# MicroSD.net
KiCad netlist of a schematic drawn in Altium Designer
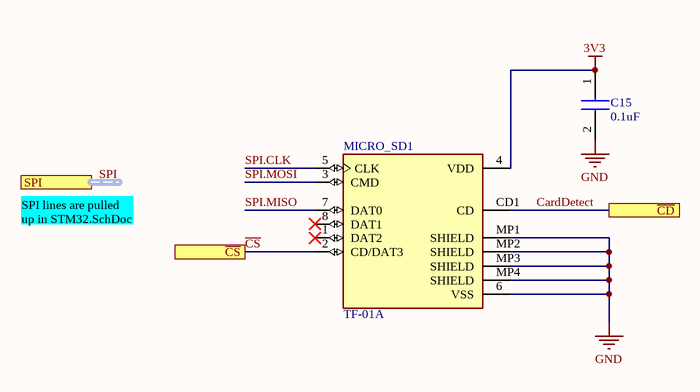
[diagram p0: MicroSD.SchDoc]

(export (version "E")
  (design (tool "Eeschema 10.0.6"))
  (components
    (comp (ref "C15")
      (value "0.1uF")
      (footprint "SamacSys:CAPC1005X55N")
      (description "0.1uF Ceramic Capacitor")
      (fields
        (field (name "MANUFACTURER_PART_NUMBER") "CL05B104KO5NNNC")
        (field (name "MOUSER PART NUMBER") "187-CL05B104KO5NNNC")
      )
      (libsource (lib "SamacSys") (part "CL05B104KO5NNNC"))
    )
    (comp (ref "MICRO_SD1")
      (value "TF-01A")
      (footprint "TF-01A")
      (description "Standard Card Edge Connectors")
      (fields (field (name "MF") "HRO Electronics Co., Ltd."))
      (libsource (lib "TF-01A") (part "TF-01A"))
    )
  )
  (nets
    (net (code "2") (name "/CardDetect") (class "Default")
      (node (ref "MICRO_SD1") (pin "CD1") (pinfunction "CD_CD1") (pintype "passive"))
    )
    (net (code "3") (name "/SPI.CLK") (class "Default")
      (node (ref "MICRO_SD1") (pin "5") (pinfunction "CLK_5") (pintype "bidirectional"))
    )
    (net (code "4") (name "/SPI.MISO") (class "Default")
      (node (ref "MICRO_SD1") (pin "7") (pinfunction "DAT0_7") (pintype "bidirectional"))
    )
    (net (code "5") (name "/SPI.MOSI") (class "Default")
      (node (ref "MICRO_SD1") (pin "3") (pinfunction "CMD_3") (pintype "bidirectional"))
    )
    (net (code "7") (name "/~{CS}") (class "Default")
      (node (ref "MICRO_SD1") (pin "2") (pinfunction "CD/DAT3_2") (pintype "bidirectional"))
    )
    (net (code "8") (name "3V3") (class "Default")
      (node (ref "C15") (pin "1") (pinfunction "1_1") (pintype "passive"))
      (node (ref "MICRO_SD1") (pin "4") (pinfunction "VDD_4") (pintype "power_in"))
    )
    (net (code "9") (name "GND") (class "Default")
      (node (ref "C15") (pin "2") (pinfunction "2_2") (pintype "passive"))
      (node (ref "MICRO_SD1") (pin "6") (pinfunction "VSS_6") (pintype "power_in"))
      (node (ref "MICRO_SD1") (pin "MP1") (pinfunction "SHIELD_MP1") (pintype "power_in"))
      (node (ref "MICRO_SD1") (pin "MP2") (pinfunction "SHIELD_MP2") (pintype "power_in"))
      (node (ref "MICRO_SD1") (pin "MP3") (pinfunction "SHIELD_MP3") (pintype "power_in"))
      (node (ref "MICRO_SD1") (pin "MP4") (pinfunction "SHIELD_MP4") (pintype "power_in"))
    )
    (net (code "10") (name "unconnected-(MICRO_SD1-DAT1-Pad8)") (class "Default")
      (node (ref "MICRO_SD1") (pin "8") (pinfunction "DAT1_8") (pintype "bidirectional+no_connect"))
    )
    (net (code "11") (name "unconnected-(MICRO_SD1-DAT2-Pad1)") (class "Default")
      (node (ref "MICRO_SD1") (pin "1") (pinfunction "DAT2_1") (pintype "bidirectional+no_connect"))
    )
  )
)
